# main.net
KiCad netlist of a schematic drawn in Altium Designer
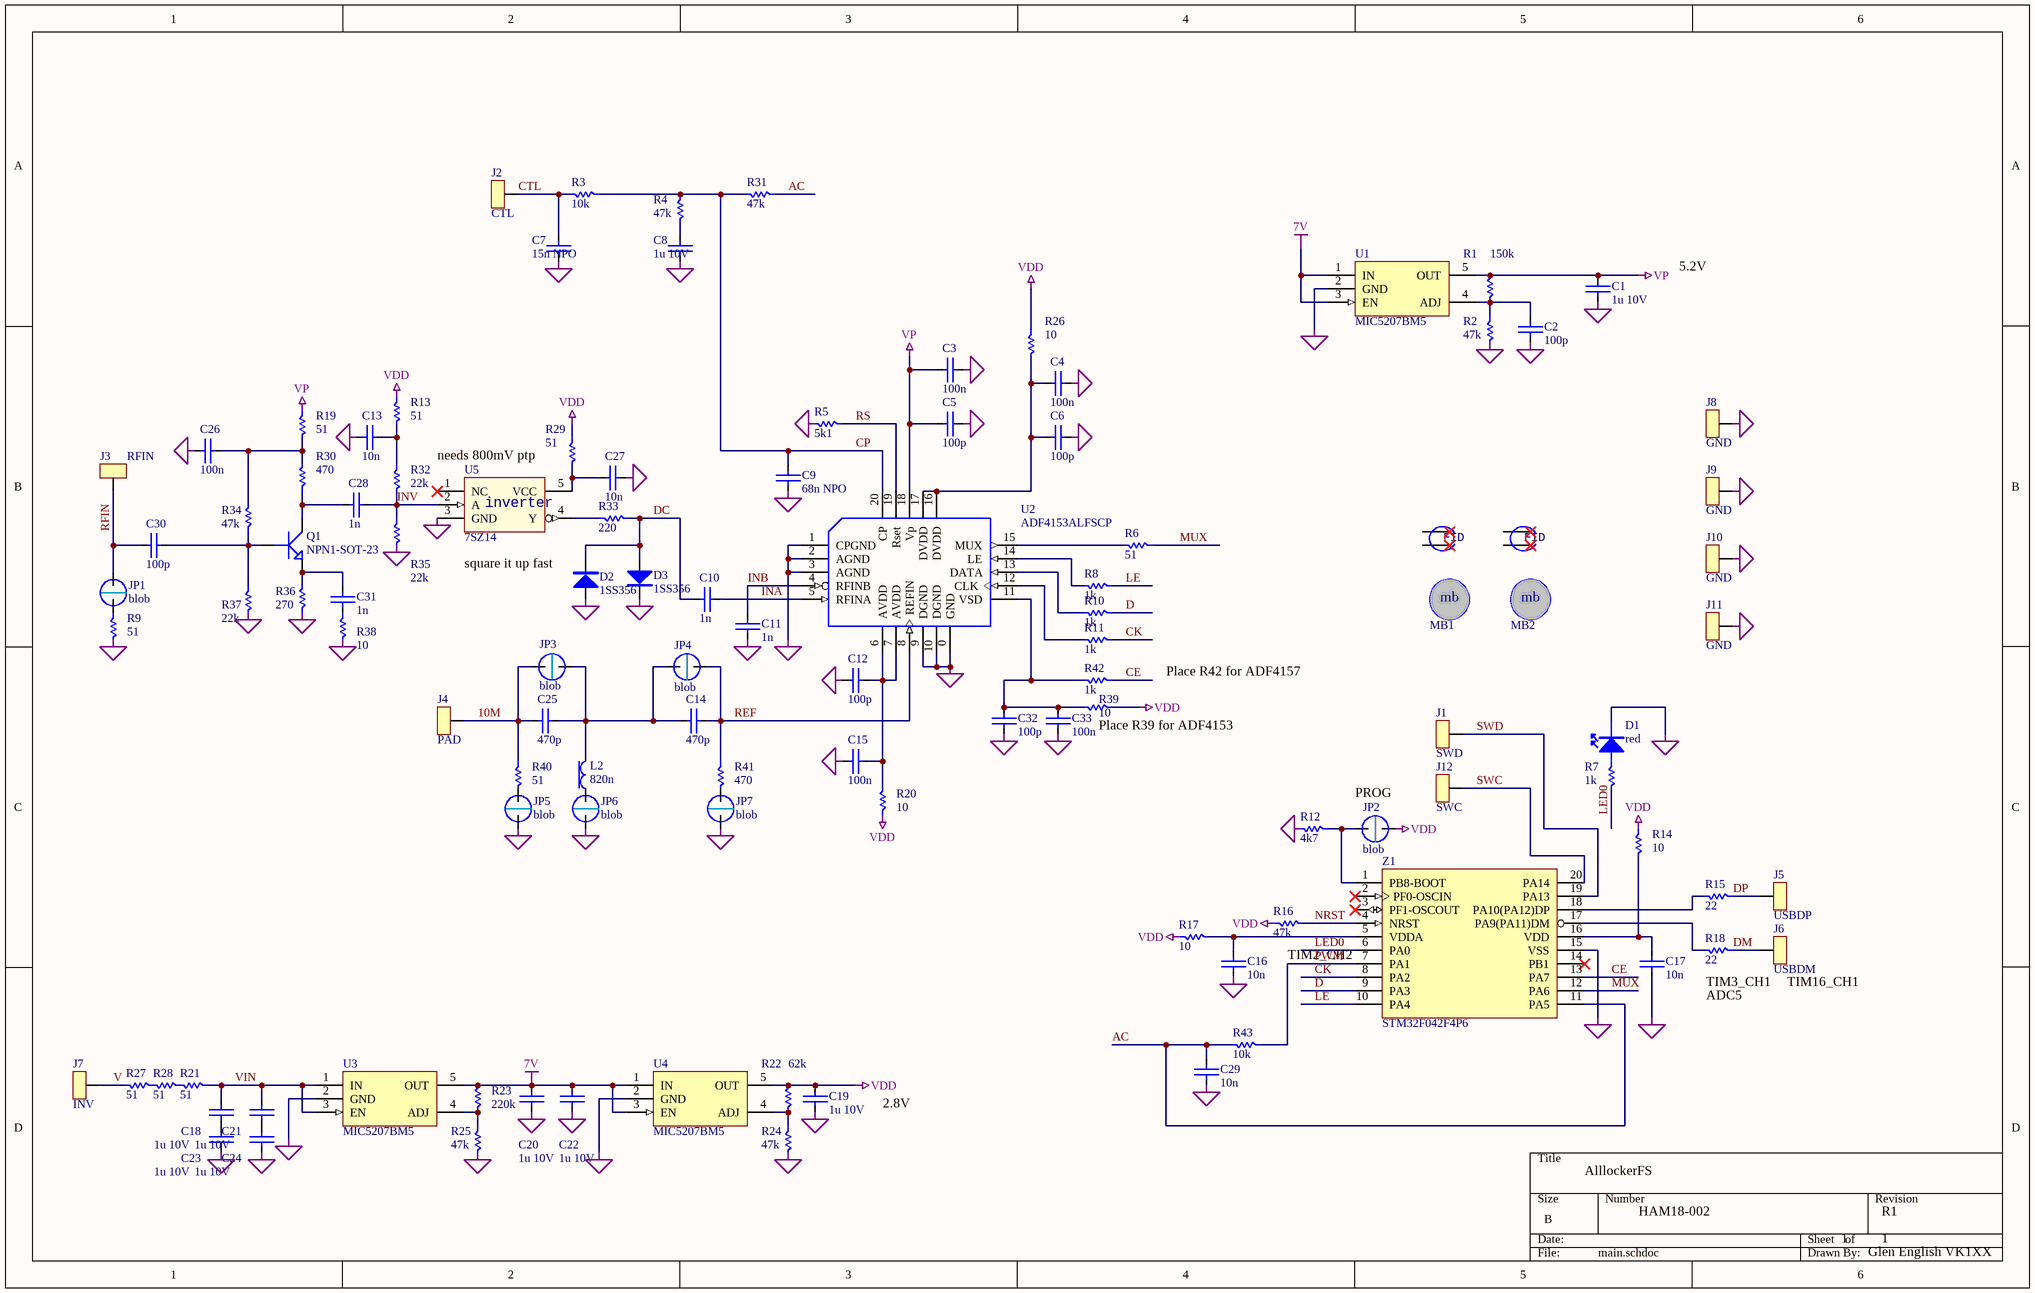
[diagram p0: main.schdoc]

(export (version "E")
  (design (tool "Eeschema 10.0.6"))
  (components
    (comp (ref "C1") (value "1u 10V") (footprint "glensPCB:0402C") (libsource (lib "glen_sch") (part "CAPS")))
    (comp (ref "C2") (value "100p") (footprint "glensPCB:0402C") (libsource (lib "glen_sch") (part "CAPS")))
    (comp (ref "C3") (value "100n") (footprint "glensPCB:0402C") (libsource (lib "glen_sch") (part "CAPS")))
    (comp (ref "C4") (value "100n") (footprint "glensPCB:0402C") (libsource (lib "glen_sch") (part "CAPS")))
    (comp (ref "C5") (value "100p") (footprint "glensPCB:0402C") (libsource (lib "glen_sch") (part "CAPS")))
    (comp (ref "C6") (value "100p") (footprint "glensPCB:0402C") (libsource (lib "glen_sch") (part "CAPS")))
    (comp (ref "C7")
      (value "15n NPO")
      (footprint "glensPCB:1206C")
      (libsource (lib "glen_sch") (part "CAPS"))
    )
    (comp (ref "C8") (value "1u 10V") (footprint "glensPCB:1206C") (libsource (lib "glen_sch") (part "CAPS")))
    (comp (ref "C9")
      (value "68n NPO")
      (footprint "glensPCB:1206C")
      (libsource (lib "glen_sch") (part "CAPS"))
    )
    (comp (ref "C10") (value "1n") (footprint "glensPCB:0402C") (libsource (lib "glen_sch") (part "CAPS")))
    (comp (ref "C11") (value "1n") (footprint "glensPCB:0402C") (libsource (lib "glen_sch") (part "CAPS")))
    (comp (ref "C12") (value "100p") (footprint "glensPCB:0402C") (libsource (lib "glen_sch") (part "CAPS")))
    (comp (ref "C13") (value "10n") (footprint "glensPCB:0402C") (libsource (lib "glen_sch") (part "CAPS")))
    (comp (ref "C14") (value "470p") (footprint "glensPCB:0402C") (libsource (lib "glen_sch") (part "CAPS")))
    (comp (ref "C15") (value "100n") (footprint "glensPCB:0402C") (libsource (lib "glen_sch") (part "CAPS")))
    (comp (ref "C16") (value "10n") (footprint "glensPCB:0402C") (libsource (lib "glen_sch") (part "CAPS")))
    (comp (ref "C17") (value "10n") (footprint "glensPCB:0402C") (libsource (lib "glen_sch") (part "CAPS")))
    (comp (ref "C18")
      (value "1u 10V")
      (footprint "glensPCB:0402C")
      (libsource (lib "glen_sch") (part "CAPS"))
    )
    (comp (ref "C19")
      (value "1u 10V")
      (footprint "glensPCB:0402C")
      (libsource (lib "glen_sch") (part "CAPS"))
    )
    (comp (ref "C20")
      (value "1u 10V")
      (footprint "glensPCB:0402C")
      (libsource (lib "glen_sch") (part "CAPS"))
    )
    (comp (ref "C21")
      (value "1u 10V")
      (footprint "glensPCB:0402C")
      (libsource (lib "glen_sch") (part "CAPS"))
    )
    (comp (ref "C22")
      (value "1u 10V")
      (footprint "glensPCB:0402C")
      (libsource (lib "glen_sch") (part "CAPS"))
    )
    (comp (ref "C23")
      (value "1u 10V")
      (footprint "glensPCB:0402C")
      (libsource (lib "glen_sch") (part "CAPS"))
    )
    (comp (ref "C24")
      (value "1u 10V")
      (footprint "glensPCB:0402C")
      (libsource (lib "glen_sch") (part "CAPS"))
    )
    (comp (ref "C25") (value "470p") (footprint "glensPCB:0402C") (libsource (lib "glen_sch") (part "CAPS")))
    (comp (ref "C26") (value "100n") (footprint "glensPCB:0402C") (libsource (lib "glen_sch") (part "CAPS")))
    (comp (ref "C27") (value "10n") (footprint "glensPCB:0402C") (libsource (lib "glen_sch") (part "CAPS")))
    (comp (ref "C28") (value "1n") (footprint "glensPCB:0402C") (libsource (lib "glen_sch") (part "CAPS")))
    (comp (ref "C29") (value "10n") (footprint "glensPCB:0402C") (libsource (lib "glen_sch") (part "CAPS")))
    (comp (ref "C30") (value "100p") (footprint "glensPCB:0402C") (libsource (lib "glen_sch") (part "CAPS")))
    (comp (ref "C31") (value "1n") (footprint "glensPCB:0402C") (libsource (lib "glen_sch") (part "CAPS")))
    (comp (ref "C32") (value "100p") (footprint "glensPCB:0402C") (libsource (lib "glen_sch") (part "CAPS")))
    (comp (ref "C33") (value "100n") (footprint "glensPCB:0402C") (libsource (lib "glen_sch") (part "CAPS")))
    (comp (ref "D1") (value "red") (footprint "0603LED") (libsource (lib "glen_sch") (part "LEDS")))
    (comp (ref "D2")
      (value "1SS356")
      (footprint "SOD323")
      (description "diode small")
      (libsource (lib "glen_sch") (part "DIODE-AKPINS_SMALL"))
    )
    (comp (ref "D3")
      (value "1SS356")
      (footprint "SOD323")
      (description "diode small")
      (libsource (lib "glen_sch") (part "DIODE-AKPINS_SMALL"))
    )
    (comp (ref "FID1")
      (value "FIDUCIAL")
      (footprint "FIDUCIAL")
      (description "fiducial mark")
      (libsource (lib "glen_sch") (part "FIDUCIAL"))
    )
    (comp (ref "FID2")
      (value "FIDUCIAL")
      (footprint "FIDUCIAL")
      (description "fiducial mark")
      (libsource (lib "glen_sch") (part "FIDUCIAL"))
    )
    (comp (ref "J1")
      (value "SWD")
      (footprint "TESTPOINT_SMALL")
      (description "test point")
      (libsource (lib "glen_sch") (part "TESTPOINT"))
    )
    (comp (ref "J2")
      (value "CTL")
      (footprint "GPPAD3R")
      (description "test point")
      (libsource (lib "glen_sch") (part "TESTPOINT"))
    )
    (comp (ref "J3")
      (value "RFIN")
      (footprint "GPPAD3R")
      (description "test point")
      (libsource (lib "") (part "TESTPOINT_2"))
    )
    (comp (ref "J4")
      (value "PAD")
      (footprint "GPPAD3R")
      (description "test point")
      (libsource (lib "glen_sch") (part "TESTPOINT"))
    )
    (comp (ref "J5")
      (value "USBDP")
      (footprint "GPPAD3R")
      (description "test point")
      (libsource (lib "") (part "TESTPOINT_1"))
    )
    (comp (ref "J6")
      (value "USBDM")
      (footprint "GPPAD3R")
      (description "test point")
      (libsource (lib "") (part "TESTPOINT_1"))
    )
    (comp (ref "J7")
      (value "INV")
      (footprint "GPPAD3R")
      (description "test point")
      (libsource (lib "glen_sch") (part "TESTPOINT"))
    )
    (comp (ref "J8")
      (value "GND")
      (footprint "GPPAD3R")
      (description "test point")
      (libsource (lib "glen_sch") (part "TESTPOINT"))
    )
    (comp (ref "J9")
      (value "GND")
      (footprint "GPPAD3R")
      (description "test point")
      (libsource (lib "glen_sch") (part "TESTPOINT"))
    )
    (comp (ref "J10")
      (value "GND")
      (footprint "GPPAD3R")
      (description "test point")
      (libsource (lib "glen_sch") (part "TESTPOINT"))
    )
    (comp (ref "J11")
      (value "GND")
      (footprint "GPPAD3R")
      (description "test point")
      (libsource (lib "glen_sch") (part "TESTPOINT"))
    )
    (comp (ref "J12")
      (value "SWC")
      (footprint "TESTPOINT_SMALL")
      (description "test point")
      (libsource (lib "glen_sch") (part "TESTPOINT"))
    )
    (comp (ref "JP1")
      (value "blob")
      (footprint "BLOBJUMPER")
      (description "blob jumper")
      (libsource (lib "glen_sch") (part "BLOBJUMPER"))
    )
    (comp (ref "JP2")
      (value "blob")
      (footprint "BLOBJUMPER")
      (description "blob jumper")
      (libsource (lib "glen_sch") (part "BLOBJUMPER"))
    )
    (comp (ref "JP3")
      (value "blob")
      (footprint "BLOBJUMPER")
      (description "blob jumper")
      (libsource (lib "glen_sch") (part "BLOBJUMPER"))
    )
    (comp (ref "JP4")
      (value "blob")
      (footprint "BLOBJUMPER")
      (description "blob jumper")
      (libsource (lib "glen_sch") (part "BLOBJUMPER"))
    )
    (comp (ref "JP5")
      (value "blob")
      (footprint "BLOBJUMPER")
      (description "blob jumper")
      (libsource (lib "glen_sch") (part "BLOBJUMPER"))
    )
    (comp (ref "JP6")
      (value "blob")
      (footprint "BLOBJUMPER")
      (description "blob jumper")
      (libsource (lib "glen_sch") (part "BLOBJUMPER"))
    )
    (comp (ref "JP7")
      (value "blob")
      (footprint "BLOBJUMPER")
      (description "blob jumper")
      (libsource (lib "glen_sch") (part "BLOBJUMPER"))
    )
    (comp (ref "L2")
      (value "820n")
      (footprint "0603L")
      (description "inductor small")
      (libsource (lib "glen_sch") (part "INDSMALL"))
    )
    (comp (ref "MB1")
      (value "mousebite")
      (footprint "mousebite")
      (libsource (lib "glen_sch") (part "mousebite"))
    )
    (comp (ref "MB2")
      (value "mousebite")
      (footprint "mousebite")
      (libsource (lib "glen_sch") (part "mousebite"))
    )
    (comp (ref "Q1")
      (value "NPN1-SOT-23")
      (footprint "SOT-323")
      (libsource (lib "glen_sch") (part "NPN1-SOT-23"))
    )
    (comp (ref "R1")
      (value "150k")
      (footprint "0402R")
      (description "resistor small")
      (libsource (lib "glen_sch") (part "RESS"))
    )
    (comp (ref "R2")
      (value "47k")
      (footprint "0402R")
      (description "resistor small")
      (libsource (lib "glen_sch") (part "RESS"))
    )
    (comp (ref "R3")
      (value "10k")
      (footprint "0603R")
      (description "resistor small")
      (libsource (lib "glen_sch") (part "RESS"))
    )
    (comp (ref "R4")
      (value "47k")
      (footprint "0603R")
      (description "resistor small")
      (libsource (lib "glen_sch") (part "RESS"))
    )
    (comp (ref "R5")
      (value "5k1")
      (footprint "0402R")
      (description "resistor small")
      (libsource (lib "glen_sch") (part "RESS"))
    )
    (comp (ref "R6")
      (value "51")
      (footprint "0402R")
      (description "resistor small")
      (libsource (lib "glen_sch") (part "RESS"))
    )
    (comp (ref "R7")
      (value "1k")
      (footprint "0402R")
      (description "resistor small")
      (libsource (lib "glen_sch") (part "RESS"))
    )
    (comp (ref "R8")
      (value "1k")
      (footprint "0402R")
      (description "resistor small")
      (libsource (lib "glen_sch") (part "RESS"))
    )
    (comp (ref "R9")
      (value "51")
      (footprint "0402R")
      (description "resistor small")
      (libsource (lib "glen_sch") (part "RESS"))
    )
    (comp (ref "R10")
      (value "1k")
      (footprint "0402R")
      (description "resistor small")
      (libsource (lib "glen_sch") (part "RESS"))
    )
    (comp (ref "R11")
      (value "1k")
      (footprint "0402R")
      (description "resistor small")
      (libsource (lib "glen_sch") (part "RESS"))
    )
    (comp (ref "R12")
      (value "4k7")
      (footprint "0402R")
      (description "resistor small")
      (libsource (lib "glen_sch") (part "RESS"))
    )
    (comp (ref "R13")
      (value "51")
      (footprint "0402R")
      (description "resistor small")
      (libsource (lib "glen_sch") (part "RESS"))
    )
    (comp (ref "R14")
      (value "10")
      (footprint "0402R")
      (description "resistor small")
      (libsource (lib "glen_sch") (part "RESS"))
    )
    (comp (ref "R15")
      (value "22")
      (footprint "0402R")
      (description "resistor small")
      (libsource (lib "glen_sch") (part "RESS"))
    )
    (comp (ref "R16")
      (value "47k")
      (footprint "0402R")
      (description "resistor small")
      (libsource (lib "glen_sch") (part "RESS"))
    )
    (comp (ref "R17")
      (value "10")
      (footprint "0402R")
      (description "resistor small")
      (libsource (lib "glen_sch") (part "RESS"))
    )
    (comp (ref "R18")
      (value "22")
      (footprint "0402R")
      (description "resistor small")
      (libsource (lib "glen_sch") (part "RESS"))
    )
    (comp (ref "R19")
      (value "51")
      (footprint "0402R")
      (description "resistor small")
      (libsource (lib "glen_sch") (part "RESS"))
    )
    (comp (ref "R20")
      (value "10")
      (footprint "0402R")
      (description "resistor small")
      (libsource (lib "glen_sch") (part "RESS"))
    )
    (comp (ref "R21")
      (value "51")
      (footprint "0402R")
      (description "resistor small")
      (libsource (lib "glen_sch") (part "RESS"))
    )
    (comp (ref "R22")
      (value "62k")
      (footprint "0402R")
      (description "resistor small")
      (libsource (lib "glen_sch") (part "RESS"))
    )
    (comp (ref "R23")
      (value "220k")
      (footprint "0402R")
      (description "resistor small")
      (libsource (lib "glen_sch") (part "RESS"))
    )
    (comp (ref "R24")
      (value "47k")
      (footprint "0402R")
      (description "resistor small")
      (libsource (lib "glen_sch") (part "RESS"))
    )
    (comp (ref "R25")
      (value "47k")
      (footprint "0402R")
      (description "resistor small")
      (libsource (lib "glen_sch") (part "RESS"))
    )
    (comp (ref "R26")
      (value "10")
      (footprint "0402R")
      (description "resistor small")
      (libsource (lib "glen_sch") (part "RESS"))
    )
    (comp (ref "R27")
      (value "51")
      (footprint "0402R")
      (description "resistor small")
      (libsource (lib "glen_sch") (part "RESS"))
    )
    (comp (ref "R28")
      (value "51")
      (footprint "0402R")
      (description "resistor small")
      (libsource (lib "glen_sch") (part "RESS"))
    )
    (comp (ref "R29")
      (value "51")
      (footprint "0402R")
      (description "resistor small")
      (libsource (lib "glen_sch") (part "RESS"))
    )
    (comp (ref "R30")
      (value "470")
      (footprint "0402R")
      (description "resistor small")
      (libsource (lib "glen_sch") (part "RESS"))
    )
    (comp (ref "R31")
      (value "47k")
      (footprint "0402R")
      (description "resistor small")
      (libsource (lib "glen_sch") (part "RESS"))
    )
    (comp (ref "R32")
      (value "22k")
      (footprint "0402R")
      (description "resistor small")
      (libsource (lib "glen_sch") (part "RESS"))
    )
    (comp (ref "R33")
      (value "220")
      (footprint "0402R")
      (description "resistor small")
      (libsource (lib "glen_sch") (part "RESS"))
    )
    (comp (ref "R34")
      (value "47k")
      (footprint "0402R")
      (description "resistor small")
      (libsource (lib "glen_sch") (part "RESS"))
    )
    (comp (ref "R35")
      (value "22k")
      (footprint "0402R")
      (description "resistor small")
      (libsource (lib "glen_sch") (part "RESS"))
    )
    (comp (ref "R36")
      (value "270")
      (footprint "0402R")
      (description "resistor small")
      (libsource (lib "glen_sch") (part "RESS"))
    )
    (comp (ref "R37")
      (value "22k")
      (footprint "0402R")
      (description "resistor small")
      (libsource (lib "glen_sch") (part "RESS"))
    )
    (comp (ref "R38")
      (value "10")
      (footprint "0402R")
      (description "resistor small")
      (libsource (lib "glen_sch") (part "RESS"))
    )
    (comp (ref "R39")
      (value "10")
      (footprint "0402R")
      (description "resistor small")
      (libsource (lib "glen_sch") (part "RESS"))
    )
    (comp (ref "R40")
      (value "51")
      (footprint "0402R")
      (description "resistor small")
      (libsource (lib "glen_sch") (part "RESS"))
    )
    (comp (ref "R41")
      (value "470")
      (footprint "0402R")
      (description "resistor small")
      (libsource (lib "glen_sch") (part "RESS"))
    )
    (comp (ref "R42")
      (value "1k")
      (footprint "0402R")
      (description "resistor small")
      (libsource (lib "glen_sch") (part "RESS"))
    )
    (comp (ref "R43")
      (value "10k")
      (footprint "0402R")
      (description "resistor small")
      (libsource (lib "glen_sch") (part "RESS"))
    )
    (comp (ref "U1")
      (value "MIC5207BM5")
      (footprint "SOT23-5")
      (description "adjustable low dropout regulator")
      (libsource (lib "glen_sch") (part "MIC5207BM5"))
    )
    (comp (ref "U2")
      (value "ADF4153ALFSCP")
      (footprint "ADI-CP-20-6")
      (description "freq synthesiser")
      (libsource (lib "glen_sch") (part "ADF4153LFSCP"))
    )
    (comp (ref "U3")
      (value "MIC5207BM5")
      (footprint "SOT23-5")
      (description "adjustable low dropout regulator")
      (libsource (lib "glen_sch") (part "MIC5207BM5"))
    )
    (comp (ref "U4")
      (value "MIC5207BM5")
      (footprint "SOT23-5")
      (description "adjustable low dropout regulator")
      (libsource (lib "glen_sch") (part "MIC5207BM5"))
    )
    (comp (ref "U5")
      (value "7SZ14")
      (footprint "SC70-5")
      (description "tinylogic unbuffer")
      (libsource (lib "glen_sch") (part "7SZ04"))
    )
    (comp (ref "Z1")
      (value "STM32F042F4P6")
      (footprint "TSSOP20_4.4mm")
      (description "STM32 M0 TSSOP")
      (libsource (lib "glen_sch") (part "STM32F042x4"))
    )
  )
  (nets
    (net (code "1") (name "/10M") (class "Default")
      (node (ref "C25") (pin "1") (pintype "passive"))
      (node (ref "J4") (pin "1") (pinfunction "TP_1") (pintype "passive"))
      (node (ref "JP3") (pin "1") (pinfunction "1_1") (pintype "passive"))
      (node (ref "R40") (pin "1") (pinfunction "1_1") (pintype "passive"))
    )
    (net (code "2") (name "/AC") (class "Default")
      (node (ref "C29") (pin "1") (pintype "passive"))
      (node (ref "R31") (pin "1") (pinfunction "1_1") (pintype "passive"))
      (node (ref "R43") (pin "2") (pinfunction "2_2") (pintype "passive"))
      (node (ref "Z1") (pin "11") (pinfunction "PA5_11") (pintype "passive"))
    )
    (net (code "3") (name "/CE") (class "Default")
      (node (ref "R42") (pin "1") (pinfunction "1_1") (pintype "passive"))
      (node (ref "Z1") (pin "13") (pinfunction "PA7_13") (pintype "passive"))
    )
    (net (code "4") (name "/CK") (class "Default")
      (node (ref "R11") (pin "1") (pinfunction "1_1") (pintype "passive"))
      (node (ref "Z1") (pin "8") (pinfunction "PA2_8") (pintype "passive"))
    )
    (net (code "5") (name "/CP") (class "Default")
      (node (ref "C9") (pin "1") (pintype "passive"))
      (node (ref "R3") (pin "1") (pinfunction "1_1") (pintype "passive"))
      (node (ref "R31") (pin "2") (pinfunction "2_2") (pintype "passive"))
      (node (ref "R4") (pin "1") (pinfunction "1_1") (pintype "passive"))
      (node (ref "U2") (pin "20") (pinfunction "CP_20") (pintype "passive"))
    )
    (net (code "6") (name "/CTL") (class "Default")
      (node (ref "C7") (pin "1") (pintype "passive"))
      (node (ref "J2") (pin "1") (pinfunction "TP_1") (pintype "passive"))
      (node (ref "R3") (pin "2") (pinfunction "2_2") (pintype "passive"))
    )
    (net (code "7") (name "/D") (class "Default")
      (node (ref "R10") (pin "1") (pinfunction "1_1") (pintype "passive"))
      (node (ref "Z1") (pin "9") (pinfunction "PA3_9") (pintype "passive"))
    )
    (net (code "8") (name "/DC") (class "Default")
      (node (ref "C10") (pin "1") (pintype "passive"))
      (node (ref "D2") (pin "K") (pinfunction "K_K") (pintype "passive"))
      (node (ref "D3") (pin "A") (pinfunction "A_A") (pintype "passive"))
      (node (ref "R33") (pin "2") (pinfunction "2_2") (pintype "passive"))
    )
    (net (code "9") (name "/DM") (class "Default")
      (node (ref "J6") (pin "1") (pinfunction "TP_1") (pintype "passive"))
      (node (ref "R18") (pin "1") (pinfunction "1_1") (pintype "passive"))
    )
    (net (code "10") (name "/DP") (class "Default")
      (node (ref "J5") (pin "1") (pinfunction "TP_1") (pintype "passive"))
      (node (ref "R15") (pin "1") (pinfunction "1_1") (pintype "passive"))
    )
    (net (code "11") (name "/INA") (class "Default")
      (node (ref "C10") (pin "2") (pintype "passive"))
      (node (ref "U2") (pin "5") (pinfunction "RFINA_5") (pintype "input"))
    )
    (net (code "12") (name "/INB") (class "Default")
      (node (ref "C11") (pin "1") (pintype "passive"))
      (node (ref "U2") (pin "4") (pinfunction "RFINB_4") (pintype "input"))
    )
    (net (code "13") (name "/INV") (class "Default")
      (node (ref "C28") (pin "2") (pintype "passive"))
      (node (ref "R32") (pin "2") (pinfunction "2_2") (pintype "passive"))
      (node (ref "R35") (pin "1") (pinfunction "1_1") (pintype "passive"))
      (node (ref "U5") (pin "2") (pinfunction "A_2") (pintype "input"))
    )
    (net (code "14") (name "/LE") (class "Default")
      (node (ref "R8") (pin "1") (pinfunction "1_1") (pintype "passive"))
      (node (ref "Z1") (pin "10") (pinfunction "PA4_10") (pintype "passive"))
    )
    (net (code "15") (name "/LED0") (class "Default")
      (node (ref "R7") (pin "2") (pinfunction "2_2") (pintype "passive"))
      (node (ref "Z1") (pin "6") (pinfunction "PA0_6") (pintype "passive"))
    )
    (net (code "16") (name "/MUX") (class "Default")
      (node (ref "R6") (pin "1") (pinfunction "1_1") (pintype "passive"))
      (node (ref "Z1") (pin "12") (pinfunction "PA6_12") (pintype "passive"))
    )
    (net (code "17") (name "/NRST") (class "Default")
      (node (ref "R16") (pin "2") (pinfunction "2_2") (pintype "passive"))
      (node (ref "Z1") (pin "4") (pinfunction "NRST_4") (pintype "input"))
    )
    (net (code "18") (name "/PWM") (class "Default")
      (node (ref "R43") (pin "1") (pinfunction "1_1") (pintype "passive"))
      (node (ref "Z1") (pin "7") (pinfunction "PA1_7") (pintype "passive"))
    )
    (net (code "19") (name "/REF") (class "Default")
      (node (ref "C14") (pin "2") (pintype "passive"))
      (node (ref "JP4") (pin "1") (pinfunction "1_1") (pintype "passive"))
      (node (ref "R41") (pin "1") (pinfunction "1_1") (pintype "passive"))
      (node (ref "U2") (pin "8") (pinfunction "REFIN_8") (pintype "input"))
    )
    (net (code "20") (name "/RFIN") (class "Default")
      (node (ref "C30") (pin "1") (pintype "passive"))
      (node (ref "J3") (pin "1") (pinfunction "TP_1") (pintype "passive"))
      (node (ref "JP1") (pin "1") (pinfunction "1_1") (pintype "passive"))
    )
    (net (code "21") (name "/RS") (class "Default")
      (node (ref "R5") (pin "1") (pinfunction "1_1") (pintype "passive"))
      (node (ref "U2") (pin "19") (pinfunction "Rset_19") (pintype "passive"))
    )
    (net (code "22") (name "/SWC") (class "Default")
      (node (ref "J12") (pin "1") (pinfunction "TP_1") (pintype "passive"))
      (node (ref "Z1") (pin "20") (pinfunction "PA14_20") (pintype "passive"))
    )
    (net (code "23") (name "/SWD") (class "Default")
      (node (ref "J1") (pin "1") (pinfunction "TP_1") (pintype "passive"))
      (node (ref "Z1") (pin "19") (pinfunction "PA13_19") (pintype "passive"))
    )
    (net (code "24") (name "/V") (class "Default")
      (node (ref "J7") (pin "1") (pinfunction "TP_1") (pintype "passive"))
      (node (ref "R27") (pin "2") (pinfunction "2_2") (pintype "passive"))
    )
    (net (code "25") (name "/VIN") (class "Default")
      (node (ref "C18") (pin "1") (pintype "passive"))
      (node (ref "C21") (pin "1") (pintype "passive"))
      (node (ref "R21") (pin "1") (pinfunction "1_1") (pintype "passive"))
      (node (ref "U3") (pin "1") (pinfunction "IN_1") (pintype "passive"))
      (node (ref "U3") (pin "3") (pinfunction "EN_3") (pintype "input"))
    )
    (net (code "26") (name "7V") (class "Default")
      (node (ref "C20") (pin "1") (pintype "passive"))
      (node (ref "C22") (pin "1") (pintype "passive"))
      (node (ref "R23") (pin "2") (pinfunction "2_2") (pintype "passive"))
      (node (ref "U1") (pin "1") (pinfunction "IN_1") (pintype "passive"))
      (node (ref "U1") (pin "3") (pinfunction "EN_3") (pintype "input"))
      (node (ref "U3") (pin "5") (pinfunction "OUT_5") (pintype "passive"))
      (node (ref "U4") (pin "1") (pinfunction "IN_1") (pintype "passive"))
      (node (ref "U4") (pin "3") (pinfunction "EN_3") (pintype "input"))
    )
    (net (code "27") (name "GND") (class "Default")
      (node (ref "C1") (pin "2") (pintype "passive"))
      (node (ref "C11") (pin "2") (pintype "passive"))
      (node (ref "C12") (pin "1") (pintype "passive"))
      (node (ref "C13") (pin "1") (pintype "passive"))
      (node (ref "C15") (pin "1") (pintype "passive"))
      (node (ref "C16") (pin "2") (pintype "passive"))
      (node (ref "C17") (pin "2") (pintype "passive"))
      (node (ref "C19") (pin "2") (pintype "passive"))
      (node (ref "C2") (pin "2") (pintype "passive"))
      (node (ref "C20") (pin "2") (pintype "passive"))
      (node (ref "C22") (pin "2") (pintype "passive"))
      (node (ref "C23") (pin "2") (pintype "passive"))
      (node (ref "C24") (pin "2") (pintype "passive"))
      (node (ref "C26") (pin "1") (pintype "passive"))
      (node (ref "C27") (pin "2") (pintype "passive"))
      (node (ref "C29") (pin "2") (pintype "passive"))
      (node (ref "C3") (pin "2") (pintype "passive"))
      (node (ref "C32") (pin "2") (pintype "passive"))
      (node (ref "C33") (pin "2") (pintype "passive"))
      (node (ref "C4") (pin "2") (pintype "passive"))
      (node (ref "C5") (pin "2") (pintype "passive"))
      (node (ref "C6") (pin "2") (pintype "passive"))
      (node (ref "C7") (pin "2") (pintype "passive"))
      (node (ref "C8") (pin "2") (pintype "passive"))
      (node (ref "C9") (pin "2") (pintype "passive"))
      (node (ref "D1") (pin "K") (pintype "passive"))
      (node (ref "D2") (pin "A") (pinfunction "A_A") (pintype "passive"))
      (node (ref "D3") (pin "K") (pinfunction "K_K") (pintype "passive"))
      (node (ref "J10") (pin "1") (pinfunction "TP_1") (pintype "passive"))
      (node (ref "J11") (pin "1") (pinfunction "TP_1") (pintype "passive"))
      (node (ref "J8") (pin "1") (pinfunction "TP_1") (pintype "passive"))
      (node (ref "J9") (pin "1") (pinfunction "TP_1") (pintype "passive"))
      (node (ref "JP5") (pin "2") (pinfunction "2_2") (pintype "passive"))
      (node (ref "JP6") (pin "2") (pinfunction "2_2") (pintype "passive"))
      (node (ref "JP7") (pin "2") (pinfunction "2_2") (pintype "passive"))
      (node (ref "R12") (pin "2") (pinfunction "2_2") (pintype "passive"))
      (node (ref "R2") (pin "2") (pinfunction "2_2") (pintype "passive"))
      (node (ref "R24") (pin "2") (pinfunction "2_2") (pintype "passive"))
      (node (ref "R25") (pin "2") (pinfunction "2_2") (pintype "passive"))
      (node (ref "R35") (pin "2") (pinfunction "2_2") (pintype "passive"))
      (node (ref "R36") (pin "1") (pinfunction "1_1") (pintype "passive"))
      (node (ref "R37") (pin "2") (pinfunction "2_2") (pintype "passive"))
      (node (ref "R38") (pin "2") (pinfunction "2_2") (pintype "passive"))
      (node (ref "R5") (pin "2") (pinfunction "2_2") (pintype "passive"))
      (node (ref "R9") (pin "2") (pinfunction "2_2") (pintype "passive"))
      (node (ref "U1") (pin "2") (pinfunction "GND_2") (pintype "passive"))
      (node (ref "U2") (pin "0") (pinfunction "GND_0") (pintype "passive"))
      (node (ref "U2") (pin "1") (pinfunction "CPGND_1") (pintype "passive"))
      (node (ref "U2") (pin "10") (pinfunction "DGND_10") (pintype "passive"))
      (node (ref "U2") (pin "2") (pinfunction "AGND_2") (pintype "passive"))
      (node (ref "U2") (pin "3") (pinfunction "AGND_3") (pintype "passive"))
      (node (ref "U2") (pin "9") (pinfunction "DGND_9") (pintype "passive"))
      (node (ref "U3") (pin "2") (pinfunction "GND_2") (pintype "passive"))
      (node (ref "U4") (pin "2") (pinfunction "GND_2") (pintype "passive"))
      (node (ref "U5") (pin "3") (pinfunction "GND_3") (pintype "passive"))
      (node (ref "Z1") (pin "15") (pinfunction "VSS_15") (pintype "passive"))
    )
    (net (code "28") (name "Net-(C4-Pad1)") (class "Default")
      (node (ref "C4") (pin "1") (pintype "passive"))
      (node (ref "C6") (pin "1") (pintype "passive"))
      (node (ref "R26") (pin "2") (pinfunction "2_2") (pintype "passive"))
      (node (ref "U2") (pin "16") (pinfunction "DVDD_16") (pintype "passive"))
      (node (ref "U2") (pin "17") (pinfunction "DVDD_17") (pintype "passive"))
    )
    (net (code "29") (name "Net-(C8-Pad1)") (class "Default")
      (node (ref "C8") (pin "1") (pintype "passive"))
      (node (ref "R4") (pin "2") (pinfunction "2_2") (pintype "passive"))
    )
    (net (code "30") (name "Net-(C12-Pad2)") (class "Default")
      (node (ref "C12") (pin "2") (pintype "passive"))
      (node (ref "C15") (pin "2") (pintype "passive"))
      (node (ref "R20") (pin "2") (pinfunction "2_2") (pintype "passive"))
      (node (ref "U2") (pin "6") (pinfunction "AVDD_6") (pintype "passive"))
      (node (ref "U2") (pin "7") (pinfunction "AVDD_7") (pintype "passive"))
    )
    (net (code "31") (name "Net-(C13-Pad2)") (class "Default")
      (node (ref "C13") (pin "2") (pintype "passive"))
      (node (ref "R13") (pin "2") (pinfunction "2_2") (pintype "passive"))
      (node (ref "R32") (pin "1") (pinfunction "1_1") (pintype "passive"))
    )
    (net (code "32") (name "Net-(C14-Pad1)") (class "Default")
      (node (ref "C14") (pin "1") (pintype "passive"))
      (node (ref "C25") (pin "2") (pintype "passive"))
      (node (ref "JP3") (pin "2") (pinfunction "2_2") (pintype "passive"))
      (node (ref "JP4") (pin "2") (pinfunction "2_2") (pintype "passive"))
      (node (ref "L2") (pin "2") (pintype "passive"))
    )
    (net (code "33") (name "Net-(C18-Pad2)") (class "Default")
      (node (ref "C18") (pin "2") (pintype "passive"))
      (node (ref "C23") (pin "1") (pintype "passive"))
    )
    (net (code "34") (name "Net-(C21-Pad2)") (class "Default")
      (node (ref "C21") (pin "2") (pintype "passive"))
      (node (ref "C24") (pin "1") (pintype "passive"))
    )
    (net (code "35") (name "Net-(C26-Pad2)") (class "Default")
      (node (ref "C26") (pin "2") (pintype "passive"))
      (node (ref "R19") (pin "2") (pinfunction "2_2") (pintype "passive"))
      (node (ref "R30") (pin "2") (pinfunction "2_2") (pintype "passive"))
      (node (ref "R34") (pin "2") (pinfunction "2_2") (pintype "passive"))
    )
    (net (code "36") (name "Net-(C31-Pad1)") (class "Default")
      (node (ref "C31") (pin "1") (pintype "passive"))
      (node (ref "R38") (pin "1") (pinfunction "1_1") (pintype "passive"))
    )
    (net (code "37") (name "Net-(D1-PadA)") (class "Default")
      (node (ref "D1") (pin "A") (pintype "passive"))
      (node (ref "R7") (pin "1") (pinfunction "1_1") (pintype "passive"))
    )
    (net (code "38") (name "Net-(JP1-Pad2)") (class "Default")
      (node (ref "JP1") (pin "2") (pinfunction "2_2") (pintype "passive"))
      (node (ref "R9") (pin "1") (pinfunction "1_1") (pintype "passive"))
    )
    (net (code "39") (name "Net-(JP5-Pad1)") (class "Default")
      (node (ref "JP5") (pin "1") (pinfunction "1_1") (pintype "passive"))
      (node (ref "R40") (pin "2") (pinfunction "2_2") (pintype "passive"))
    )
    (net (code "40") (name "Net-(JP6-Pad1)") (class "Default")
      (node (ref "JP6") (pin "1") (pinfunction "1_1") (pintype "passive"))
      (node (ref "L2") (pin "1") (pintype "passive"))
    )
    (net (code "41") (name "Net-(JP7-Pad1)") (class "Default")
      (node (ref "JP7") (pin "1") (pinfunction "1_1") (pintype "passive"))
      (node (ref "R41") (pin "2") (pinfunction "2_2") (pintype "passive"))
    )
    (net (code "42") (name "Net-(Q1-BASE)") (class "Default")
      (node (ref "C30") (pin "2") (pintype "passive"))
      (node (ref "Q1") (pin "1") (pinfunction "BASE_1") (pintype "passive"))
      (node (ref "R34") (pin "1") (pinfunction "1_1") (pintype "passive"))
      (node (ref "R37") (pin "1") (pinfunction "1_1") (pintype "passive"))
    )
    (net (code "43") (name "Net-(Q1-COLLECTOR)") (class "Default")
      (node (ref "C28") (pin "1") (pintype "passive"))
      (node (ref "Q1") (pin "3") (pinfunction "COLLECTOR_3") (pintype "passive"))
      (node (ref "R30") (pin "1") (pinfunction "1_1") (pintype "passive"))
    )
    (net (code "44") (name "Net-(Q1-EMITTER)") (class "Default")
      (node (ref "C31") (pin "2") (pintype "passive"))
      (node (ref "Q1") (pin "2") (pinfunction "EMITTER_2") (pintype "passive"))
      (node (ref "R36") (pin "2") (pinfunction "2_2") (pintype "passive"))
    )
    (net (code "45") (name "Net-(R21-Pad2)") (class "Default")
      (node (ref "R21") (pin "2") (pinfunction "2_2") (pintype "passive"))
      (node (ref "R28") (pin "1") (pinfunction "1_1") (pintype "passive"))
    )
    (net (code "46") (name "Net-(R27-Pad1)") (class "Default")
      (node (ref "R27") (pin "1") (pinfunction "1_1") (pintype "passive"))
      (node (ref "R28") (pin "2") (pinfunction "2_2") (pintype "passive"))
    )
    (net (code "47") (name "Net-(U1-ADJ)") (class "Default")
      (node (ref "C2") (pin "1") (pintype "passive"))
      (node (ref "R1") (pin "1") (pinfunction "1_1") (pintype "passive"))
      (node (ref "R2") (pin "1") (pinfunction "1_1") (pintype "passive"))
      (node (ref "U1") (pin "4") (pinfunction "ADJ_4") (pintype "passive"))
    )
    (net (code "48") (name "Net-(U2-CLK)") (class "Default")
      (node (ref "R11") (pin "2") (pinfunction "2_2") (pintype "passive"))
      (node (ref "U2") (pin "12") (pinfunction "CLK_12") (pintype "input"))
    )
    (net (code "49") (name "Net-(U2-DATA)") (class "Default")
      (node (ref "R10") (pin "2") (pinfunction "2_2") (pintype "passive"))
      (node (ref "U2") (pin "13") (pinfunction "DATA_13") (pintype "input"))
    )
    (net (code "50") (name "Net-(U2-LE)") (class "Default")
      (node (ref "R8") (pin "2") (pinfunction "2_2") (pintype "passive"))
      (node (ref "U2") (pin "14") (pinfunction "LE_14") (pintype "input"))
    )
    (net (code "51") (name "Net-(U2-MUX)") (class "Default")
      (node (ref "R6") (pin "2") (pinfunction "2_2") (pintype "passive"))
      (node (ref "U2") (pin "15") (pinfunction "MUX_15") (pintype "output"))
    )
    (net (code "52") (name "Net-(U2-VSD)") (class "Default")
      (node (ref "C32") (pin "1") (pintype "passive"))
      (node (ref "C33") (pin "1") (pintype "passive"))
      (node (ref "R39") (pin "2") (pinfunction "2_2") (pintype "passive"))
      (node (ref "R42") (pin "2") (pinfunction "2_2") (pintype "passive"))
      (node (ref "U2") (pin "11") (pinfunction "VSD_11") (pintype "passive"))
    )
    (net (code "53") (name "Net-(U3-ADJ)") (class "Default")
      (node (ref "R23") (pin "1") (pinfunction "1_1") (pintype "passive"))
      (node (ref "R25") (pin "1") (pinfunction "1_1") (pintype "passive"))
      (node (ref "U3") (pin "4") (pinfunction "ADJ_4") (pintype "passive"))
    )
    (net (code "54") (name "Net-(U4-ADJ)") (class "Default")
      (node (ref "R22") (pin "1") (pinfunction "1_1") (pintype "passive"))
      (node (ref "R24") (pin "1") (pinfunction "1_1") (pintype "passive"))
      (node (ref "U4") (pin "4") (pinfunction "ADJ_4") (pintype "passive"))
    )
    (net (code "55") (name "Net-(U5-VCC)") (class "Default")
      (node (ref "C27") (pin "1") (pintype "passive"))
      (node (ref "R29") (pin "2") (pinfunction "2_2") (pintype "passive"))
      (node (ref "U5") (pin "5") (pinfunction "VCC_5") (pintype "passive"))
    )
    (net (code "56") (name "Net-(U5-Y)") (class "Default")
      (node (ref "R33") (pin "1") (pinfunction "1_1") (pintype "passive"))
      (node (ref "U5") (pin "4") (pinfunction "Y_4") (pintype "output"))
    )
    (net (code "57") (name "Net-(Z1-PA9(PA11)DM)") (class "Default")
      (node (ref "R18") (pin "2") (pinfunction "2_2") (pintype "passive"))
      (node (ref "Z1") (pin "17") (pinfunction "PA9(PA11)DM_17") (pintype "passive"))
    )
    (net (code "58") (name "Net-(Z1-PA10(PA12)DP)") (class "Default")
      (node (ref "R15") (pin "2") (pinfunction "2_2") (pintype "passive"))
      (node (ref "Z1") (pin "18") (pinfunction "PA10(PA12)DP_18") (pintype "passive"))
    )
    (net (code "59") (name "Net-(Z1-PB8-BOOT)") (class "Default")
      (node (ref "JP2") (pin "2") (pinfunction "2_2") (pintype "passive"))
      (node (ref "R12") (pin "1") (pinfunction "1_1") (pintype "passive"))
      (node (ref "Z1") (pin "1") (pinfunction "PB8-BOOT_1") (pintype "passive"))
    )
    (net (code "60") (name "Net-(Z1-VDD)") (class "Default")
      (node (ref "C17") (pin "1") (pintype "passive"))
      (node (ref "R14") (pin "2") (pinfunction "2_2") (pintype "passive"))
      (node (ref "Z1") (pin "16") (pinfunction "VDD_16") (pintype "passive"))
    )
    (net (code "61") (name "Net-(Z1-VDDA)") (class "Default")
      (node (ref "C16") (pin "1") (pintype "passive"))
      (node (ref "R17") (pin "2") (pinfunction "2_2") (pintype "passive"))
      (node (ref "Z1") (pin "5") (pinfunction "VDDA_5") (pintype "passive"))
    )
    (net (code "62") (name "VDD") (class "Default")
      (node (ref "C19") (pin "1") (pintype "passive"))
      (node (ref "JP2") (pin "1") (pinfunction "1_1") (pintype "passive"))
      (node (ref "R13") (pin "1") (pinfunction "1_1") (pintype "passive"))
      (node (ref "R14") (pin "1") (pinfunction "1_1") (pintype "passive"))
      (node (ref "R16") (pin "1") (pinfunction "1_1") (pintype "passive"))
      (node (ref "R17") (pin "1") (pinfunction "1_1") (pintype "passive"))
      (node (ref "R20") (pin "1") (pinfunction "1_1") (pintype "passive"))
      (node (ref "R22") (pin "2") (pinfunction "2_2") (pintype "passive"))
      (node (ref "R26") (pin "1") (pinfunction "1_1") (pintype "passive"))
      (node (ref "R29") (pin "1") (pinfunction "1_1") (pintype "passive"))
      (node (ref "R39") (pin "1") (pinfunction "1_1") (pintype "passive"))
      (node (ref "U4") (pin "5") (pinfunction "OUT_5") (pintype "passive"))
    )
    (net (code "63") (name "VP") (class "Default")
      (node (ref "C1") (pin "1") (pintype "passive"))
      (node (ref "C3") (pin "1") (pintype "passive"))
      (node (ref "C5") (pin "1") (pintype "passive"))
      (node (ref "R1") (pin "2") (pinfunction "2_2") (pintype "passive"))
      (node (ref "R19") (pin "1") (pinfunction "1_1") (pintype "passive"))
      (node (ref "U1") (pin "5") (pinfunction "OUT_5") (pintype "passive"))
      (node (ref "U2") (pin "18") (pinfunction "Vp_18") (pintype "passive"))
    )
    (net (code "64") (name "unconnected-(FID1-Pad0)") (class "Default")
      (node (ref "FID1") (pin "0") (pinfunction "0_0") (pintype "passive+no_connect"))
    )
    (net (code "65") (name "unconnected-(FID1-Pad1)") (class "Default")
      (node (ref "FID1") (pin "1") (pinfunction "1_1") (pintype "passive+no_connect"))
    )
    (net (code "66") (name "unconnected-(FID2-Pad0)") (class "Default")
      (node (ref "FID2") (pin "0") (pinfunction "0_0") (pintype "passive+no_connect"))
    )
    (net (code "67") (name "unconnected-(FID2-Pad1)") (class "Default")
      (node (ref "FID2") (pin "1") (pinfunction "1_1") (pintype "passive+no_connect"))
    )
    (net (code "68") (name "unconnected-(U5-NC-Pad1)") (class "Default")
      (node (ref "U5") (pin "1") (pinfunction "NC_1") (pintype "passive+no_connect"))
    )
    (net (code "69") (name "unconnected-(Z1-PB1-Pad14)") (class "Default")
      (node (ref "Z1") (pin "14") (pinfunction "PB1_14") (pintype "passive+no_connect"))
    )
    (net (code "70") (name "unconnected-(Z1-PF0-OSCIN-Pad2)") (class "Default")
      (node (ref "Z1") (pin "2") (pinfunction "PF0-OSCIN_2") (pintype "input+no_connect"))
    )
    (net (code "71") (name "unconnected-(Z1-PF1-OSCOUT-Pad3)") (class "Default")
      (node (ref "Z1") (pin "3") (pinfunction "PF1-OSCOUT_3") (pintype "bidirectional+no_connect"))
    )
  )
)
